# MIX0401_Main.net
KiCad netlist of a schematic drawn in EAGLE
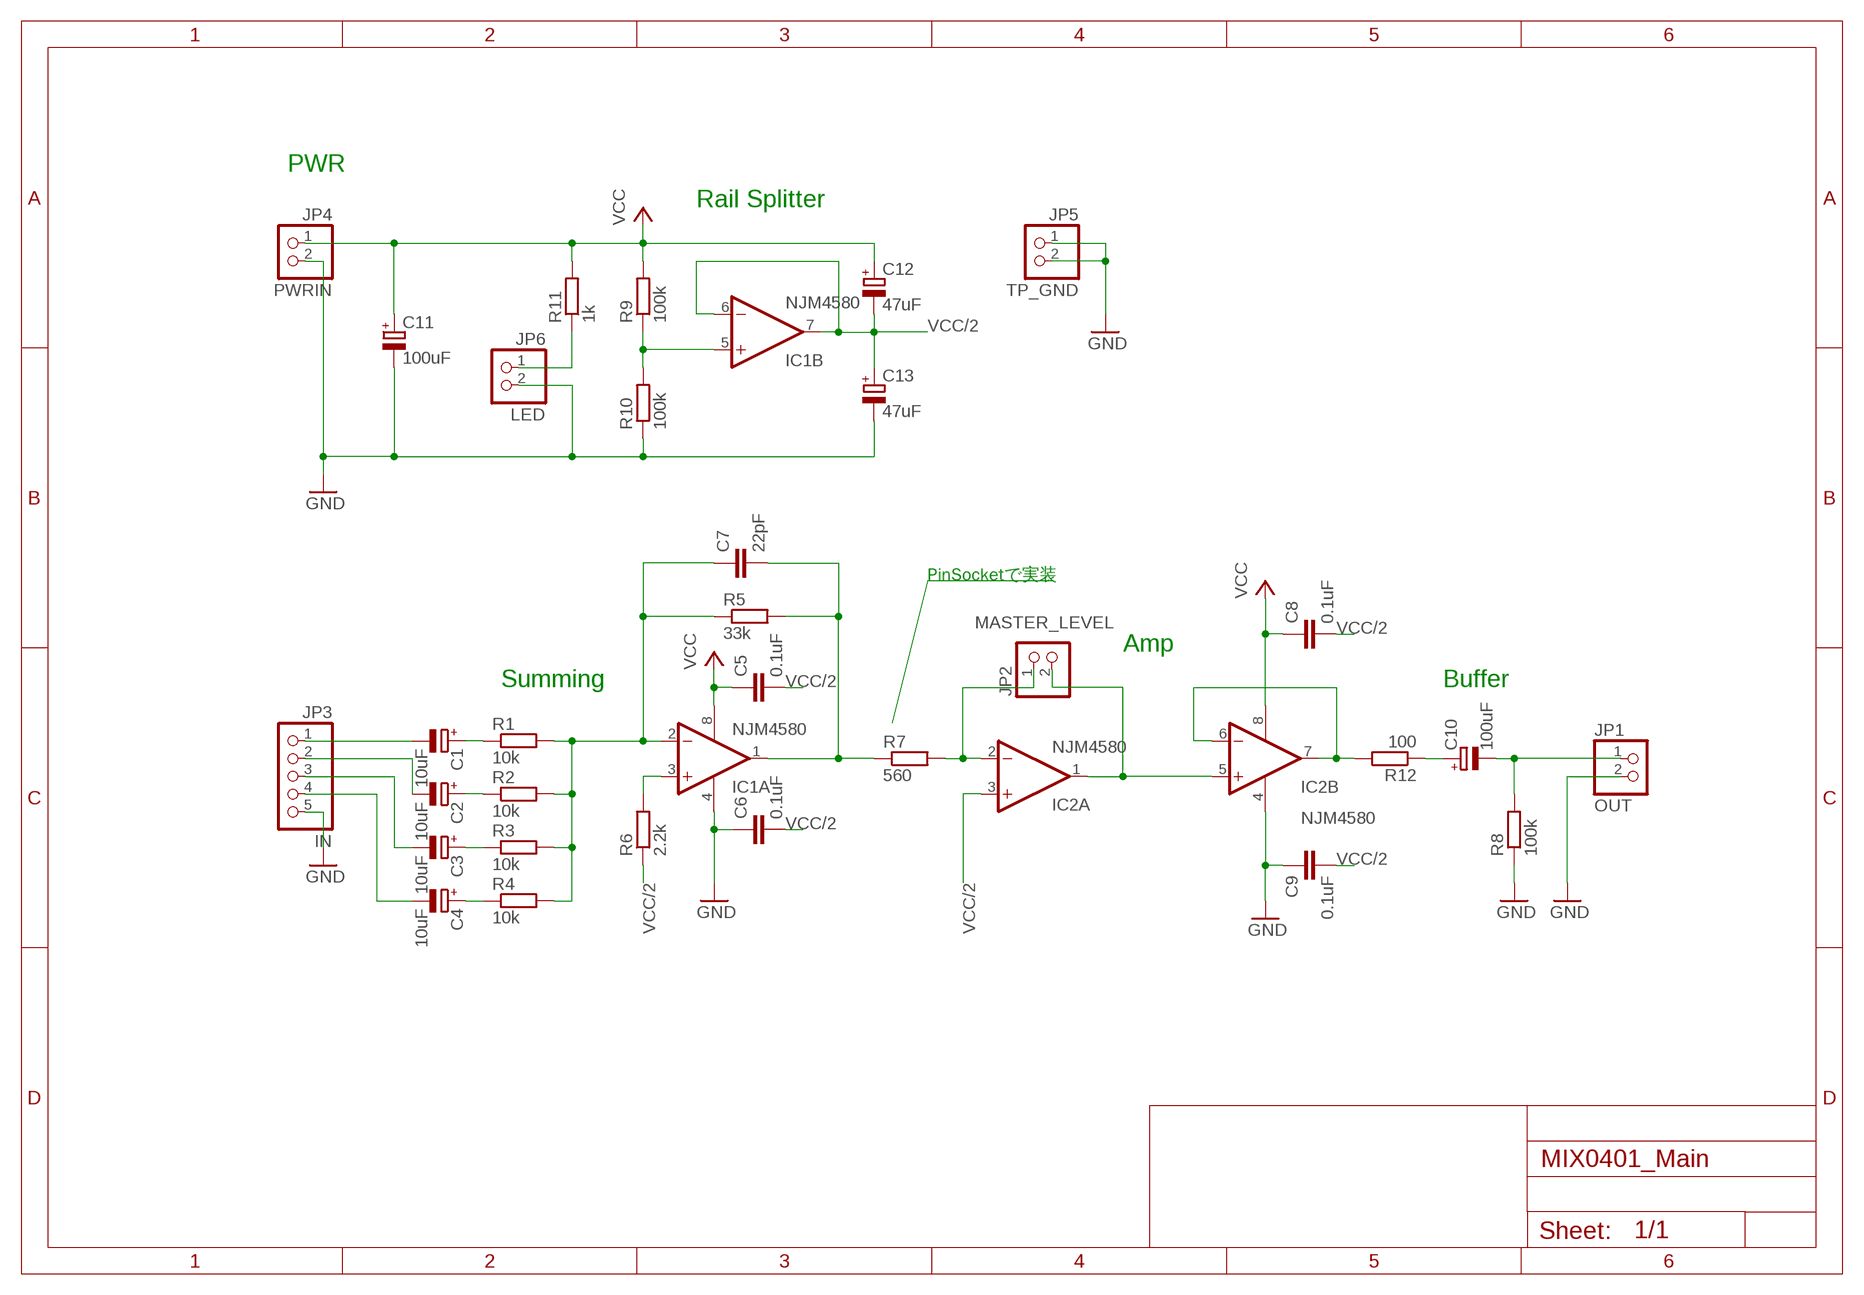
[diagram p0: schematic, sheet 1]

(export (version "E")
  (design (tool "Eeschema 10.0.6"))
  (components
    (comp (ref "C1")
      (value "10uF")
      (footprint "eagle-import:E2,5-5")
      (libsource (lib "eagle-import") (part "CPOL-EUE2.5-5"))
    )
    (comp (ref "C2")
      (value "10uF")
      (footprint "eagle-import:E2,5-5")
      (libsource (lib "eagle-import") (part "CPOL-EUE2.5-5"))
    )
    (comp (ref "C3")
      (value "10uF")
      (footprint "eagle-import:E2,5-5")
      (libsource (lib "eagle-import") (part "CPOL-EUE2.5-5"))
    )
    (comp (ref "C4")
      (value "10uF")
      (footprint "eagle-import:E2,5-5")
      (libsource (lib "eagle-import") (part "CPOL-EUE2.5-5"))
    )
    (comp (ref "C5")
      (value "0.1uF")
      (footprint "eagle-import:C025-024X044")
      (libsource (lib "eagle-import") (part "C-EU025-024X044"))
    )
    (comp (ref "C6")
      (value "0.1uF")
      (footprint "eagle-import:C025-024X044")
      (libsource (lib "eagle-import") (part "C-EU025-024X044"))
    )
    (comp (ref "C7")
      (value "22pF")
      (footprint "eagle-import:C050-024X044")
      (libsource (lib "eagle-import") (part "C-EU050-024X044"))
    )
    (comp (ref "C8")
      (value "0.1uF")
      (footprint "eagle-import:C025-024X044")
      (libsource (lib "eagle-import") (part "C-EU025-024X044"))
    )
    (comp (ref "C9")
      (value "0.1uF")
      (footprint "eagle-import:C025-024X044")
      (libsource (lib "eagle-import") (part "C-EU025-024X044"))
    )
    (comp (ref "C10")
      (value "100uF")
      (footprint "eagle-import:E2,5-7")
      (libsource (lib "eagle-import") (part "CPOL-EUE2.5-7"))
    )
    (comp (ref "C11")
      (value "100uF")
      (footprint "eagle-import:E2,5-7")
      (libsource (lib "eagle-import") (part "CPOL-EUE2.5-7"))
    )
    (comp (ref "C12")
      (value "47uF")
      (footprint "eagle-import:E2,5-6")
      (libsource (lib "eagle-import") (part "CPOL-EUE2.5-6"))
    )
    (comp (ref "C13")
      (value "47uF")
      (footprint "eagle-import:E2,5-6")
      (libsource (lib "eagle-import") (part "CPOL-EUE2.5-6"))
    )
    (comp (ref "IC1")
      (value "NJM4580")
      (footprint "eagle-import:DIL08")
      (libsource (lib "eagle-import") (part "4558NLM"))
    )
    (comp (ref "IC2")
      (value "NJM4580")
      (footprint "eagle-import:DIL08")
      (libsource (lib "eagle-import") (part "4558NLM"))
    )
    (comp (ref "JP1")
      (value "OUT")
      (footprint "eagle-import:1X02")
      (libsource (lib "eagle-import") (part "PINHD-1X2"))
    )
    (comp (ref "JP2")
      (value "MASTER_LEVEL")
      (footprint "eagle-import:1X02")
      (libsource (lib "eagle-import") (part "PINHD-1X2"))
    )
    (comp (ref "JP3")
      (value "IN")
      (footprint "eagle-import:1X05")
      (libsource (lib "eagle-import") (part "PINHD-1X5"))
    )
    (comp (ref "JP4")
      (value "PWRIN")
      (footprint "eagle-import:1X02")
      (libsource (lib "eagle-import") (part "PINHD-1X2"))
    )
    (comp (ref "JP5")
      (value "TP_GND")
      (footprint "eagle-import:1X02")
      (libsource (lib "eagle-import") (part "PINHD-1X2"))
    )
    (comp (ref "JP6")
      (value "LED")
      (footprint "eagle-import:1X02")
      (libsource (lib "eagle-import") (part "PINHD-1X2"))
    )
    (comp (ref "R1")
      (value "10k")
      (footprint "eagle-import:0207_7")
      (libsource (lib "eagle-import") (part "R-EU_0207/7"))
    )
    (comp (ref "R2")
      (value "10k")
      (footprint "eagle-import:0207_7")
      (libsource (lib "eagle-import") (part "R-EU_0207/7"))
    )
    (comp (ref "R3")
      (value "10k")
      (footprint "eagle-import:0207_7")
      (libsource (lib "eagle-import") (part "R-EU_0207/7"))
    )
    (comp (ref "R4")
      (value "10k")
      (footprint "eagle-import:0207_7")
      (libsource (lib "eagle-import") (part "R-EU_0207/7"))
    )
    (comp (ref "R5")
      (value "33k")
      (footprint "eagle-import:0207_7")
      (libsource (lib "eagle-import") (part "R-EU_0207/7"))
    )
    (comp (ref "R6")
      (value "2.2k")
      (footprint "eagle-import:0207_7")
      (libsource (lib "eagle-import") (part "R-EU_0207/7"))
    )
    (comp (ref "R7")
      (value "560")
      (footprint "eagle-import:0207_7")
      (libsource (lib "eagle-import") (part "R-EU_0207/7"))
    )
    (comp (ref "R8")
      (value "100k")
      (footprint "eagle-import:0207_7")
      (libsource (lib "eagle-import") (part "R-EU_0207/7"))
    )
    (comp (ref "R9")
      (value "100k")
      (footprint "eagle-import:0207_7")
      (libsource (lib "eagle-import") (part "R-EU_0207/7"))
    )
    (comp (ref "R10")
      (value "100k")
      (footprint "eagle-import:0207_7")
      (libsource (lib "eagle-import") (part "R-EU_0207/7"))
    )
    (comp (ref "R11")
      (value "1k")
      (footprint "eagle-import:0207_7")
      (libsource (lib "eagle-import") (part "R-EU_0207/7"))
    )
    (comp (ref "R12")
      (value "100")
      (footprint "eagle-import:0207_7")
      (libsource (lib "eagle-import") (part "R-EU_0207/7"))
    )
  )
  (nets
    (net (code "1") (name "/VCC{slash}2") (class "Default")
      (node (ref "C12") (pin "-") (pinfunction "-_-") (pintype "passive"))
      (node (ref "C13") (pin "+") (pinfunction "+_+") (pintype "passive"))
      (node (ref "C5") (pin "2") (pinfunction "2_2") (pintype "passive"))
      (node (ref "C6") (pin "2") (pinfunction "2_2") (pintype "passive"))
      (node (ref "C8") (pin "2") (pinfunction "2_2") (pintype "passive"))
      (node (ref "C9") (pin "2") (pinfunction "2_2") (pintype "passive"))
      (node (ref "IC1") (pin "6") (pinfunction "-IN_6") (pintype "input"))
      (node (ref "IC1") (pin "7") (pinfunction "OUT_7") (pintype "output"))
      (node (ref "IC2") (pin "3") (pinfunction "+IN_3") (pintype "input"))
      (node (ref "R6") (pin "1") (pinfunction "1_1") (pintype "passive"))
    )
    (net (code "2") (name "GND") (class "Default")
      (node (ref "C11") (pin "-") (pinfunction "-_-") (pintype "passive"))
      (node (ref "C13") (pin "-") (pinfunction "-_-") (pintype "passive"))
      (node (ref "C6") (pin "1") (pinfunction "1_1") (pintype "passive"))
      (node (ref "C9") (pin "1") (pinfunction "1_1") (pintype "passive"))
      (node (ref "IC1") (pin "4") (pinfunction "V-_4") (pintype "power_in"))
      (node (ref "IC2") (pin "4") (pinfunction "V-_4") (pintype "power_in"))
      (node (ref "JP1") (pin "2") (pinfunction "2_2") (pintype "passive"))
      (node (ref "JP3") (pin "5") (pinfunction "5_5") (pintype "passive"))
      (node (ref "JP4") (pin "2") (pinfunction "2_2") (pintype "passive"))
      (node (ref "JP5") (pin "1") (pinfunction "1_1") (pintype "passive"))
      (node (ref "JP5") (pin "2") (pinfunction "2_2") (pintype "passive"))
      (node (ref "JP6") (pin "2") (pinfunction "2_2") (pintype "passive"))
      (node (ref "R10") (pin "1") (pinfunction "1_1") (pintype "passive"))
      (node (ref "R8") (pin "1") (pinfunction "1_1") (pintype "passive"))
    )
    (net (code "3") (name "Net-(C1-Pad+)") (class "Default")
      (node (ref "C1") (pin "+") (pinfunction "+_+") (pintype "passive"))
      (node (ref "R1") (pin "1") (pinfunction "1_1") (pintype "passive"))
    )
    (net (code "4") (name "Net-(C1-Pad-)") (class "Default")
      (node (ref "C1") (pin "-") (pinfunction "-_-") (pintype "passive"))
      (node (ref "JP3") (pin "1") (pinfunction "1_1") (pintype "passive"))
    )
    (net (code "5") (name "Net-(C2-Pad+)") (class "Default")
      (node (ref "C2") (pin "+") (pinfunction "+_+") (pintype "passive"))
      (node (ref "R2") (pin "1") (pinfunction "1_1") (pintype "passive"))
    )
    (net (code "6") (name "Net-(C2-Pad-)") (class "Default")
      (node (ref "C2") (pin "-") (pinfunction "-_-") (pintype "passive"))
      (node (ref "JP3") (pin "2") (pinfunction "2_2") (pintype "passive"))
    )
    (net (code "7") (name "Net-(C3-Pad+)") (class "Default")
      (node (ref "C3") (pin "+") (pinfunction "+_+") (pintype "passive"))
      (node (ref "R3") (pin "1") (pinfunction "1_1") (pintype "passive"))
    )
    (net (code "8") (name "Net-(C3-Pad-)") (class "Default")
      (node (ref "C3") (pin "-") (pinfunction "-_-") (pintype "passive"))
      (node (ref "JP3") (pin "3") (pinfunction "3_3") (pintype "passive"))
    )
    (net (code "9") (name "Net-(C4-Pad+)") (class "Default")
      (node (ref "C4") (pin "+") (pinfunction "+_+") (pintype "passive"))
      (node (ref "R4") (pin "1") (pinfunction "1_1") (pintype "passive"))
    )
    (net (code "10") (name "Net-(C4-Pad-)") (class "Default")
      (node (ref "C4") (pin "-") (pinfunction "-_-") (pintype "passive"))
      (node (ref "JP3") (pin "4") (pinfunction "4_4") (pintype "passive"))
    )
    (net (code "11") (name "Net-(C10-Pad+)") (class "Default")
      (node (ref "C10") (pin "+") (pinfunction "+_+") (pintype "passive"))
      (node (ref "R12") (pin "1") (pinfunction "1_1") (pintype "passive"))
    )
    (net (code "12") (name "Net-(C10-Pad-)") (class "Default")
      (node (ref "C10") (pin "-") (pinfunction "-_-") (pintype "passive"))
      (node (ref "JP1") (pin "1") (pinfunction "1_1") (pintype "passive"))
      (node (ref "R8") (pin "2") (pinfunction "2_2") (pintype "passive"))
    )
    (net (code "13") (name "Net-(IC1A-+IN)") (class "Default")
      (node (ref "IC1") (pin "3") (pinfunction "+IN_3") (pintype "input"))
      (node (ref "R6") (pin "2") (pinfunction "2_2") (pintype "passive"))
    )
    (net (code "14") (name "Net-(IC1A--IN)") (class "Default")
      (node (ref "C7") (pin "1") (pinfunction "1_1") (pintype "passive"))
      (node (ref "IC1") (pin "2") (pinfunction "-IN_2") (pintype "input"))
      (node (ref "R1") (pin "2") (pinfunction "2_2") (pintype "passive"))
      (node (ref "R2") (pin "2") (pinfunction "2_2") (pintype "passive"))
      (node (ref "R3") (pin "2") (pinfunction "2_2") (pintype "passive"))
      (node (ref "R4") (pin "2") (pinfunction "2_2") (pintype "passive"))
      (node (ref "R5") (pin "1") (pinfunction "1_1") (pintype "passive"))
    )
    (net (code "15") (name "Net-(IC1A-OUT)") (class "Default")
      (node (ref "C7") (pin "2") (pinfunction "2_2") (pintype "passive"))
      (node (ref "IC1") (pin "1") (pinfunction "OUT_1") (pintype "output"))
      (node (ref "R5") (pin "2") (pinfunction "2_2") (pintype "passive"))
      (node (ref "R7") (pin "1") (pinfunction "1_1") (pintype "passive"))
    )
    (net (code "16") (name "Net-(IC1B-+IN)") (class "Default")
      (node (ref "IC1") (pin "5") (pinfunction "+IN_5") (pintype "input"))
      (node (ref "R10") (pin "2") (pinfunction "2_2") (pintype "passive"))
      (node (ref "R9") (pin "1") (pinfunction "1_1") (pintype "passive"))
    )
    (net (code "17") (name "Net-(IC2A--IN)") (class "Default")
      (node (ref "IC2") (pin "2") (pinfunction "-IN_2") (pintype "input"))
      (node (ref "JP2") (pin "1") (pinfunction "1_1") (pintype "passive"))
      (node (ref "R7") (pin "2") (pinfunction "2_2") (pintype "passive"))
    )
    (net (code "18") (name "Net-(IC2A-OUT)") (class "Default")
      (node (ref "IC2") (pin "1") (pinfunction "OUT_1") (pintype "output"))
      (node (ref "IC2") (pin "5") (pinfunction "+IN_5") (pintype "input"))
      (node (ref "JP2") (pin "2") (pinfunction "2_2") (pintype "passive"))
    )
    (net (code "19") (name "Net-(IC2B--IN)") (class "Default")
      (node (ref "IC2") (pin "6") (pinfunction "-IN_6") (pintype "input"))
      (node (ref "IC2") (pin "7") (pinfunction "OUT_7") (pintype "output"))
      (node (ref "R12") (pin "2") (pinfunction "2_2") (pintype "passive"))
    )
    (net (code "20") (name "Net-(JP6-Pad1)") (class "Default")
      (node (ref "JP6") (pin "1") (pinfunction "1_1") (pintype "passive"))
      (node (ref "R11") (pin "1") (pinfunction "1_1") (pintype "passive"))
    )
    (net (code "21") (name "VCC") (class "Default")
      (node (ref "C11") (pin "+") (pinfunction "+_+") (pintype "passive"))
      (node (ref "C12") (pin "+") (pinfunction "+_+") (pintype "passive"))
      (node (ref "C5") (pin "1") (pinfunction "1_1") (pintype "passive"))
      (node (ref "C8") (pin "1") (pinfunction "1_1") (pintype "passive"))
      (node (ref "IC1") (pin "8") (pinfunction "V+_8") (pintype "power_in"))
      (node (ref "IC2") (pin "8") (pinfunction "V+_8") (pintype "power_in"))
      (node (ref "JP4") (pin "1") (pinfunction "1_1") (pintype "passive"))
      (node (ref "R11") (pin "2") (pinfunction "2_2") (pintype "passive"))
      (node (ref "R9") (pin "2") (pinfunction "2_2") (pintype "passive"))
    )
  )
)
